# LAN_RJ45.net
KiCad netlist of a schematic drawn in Altium Designer
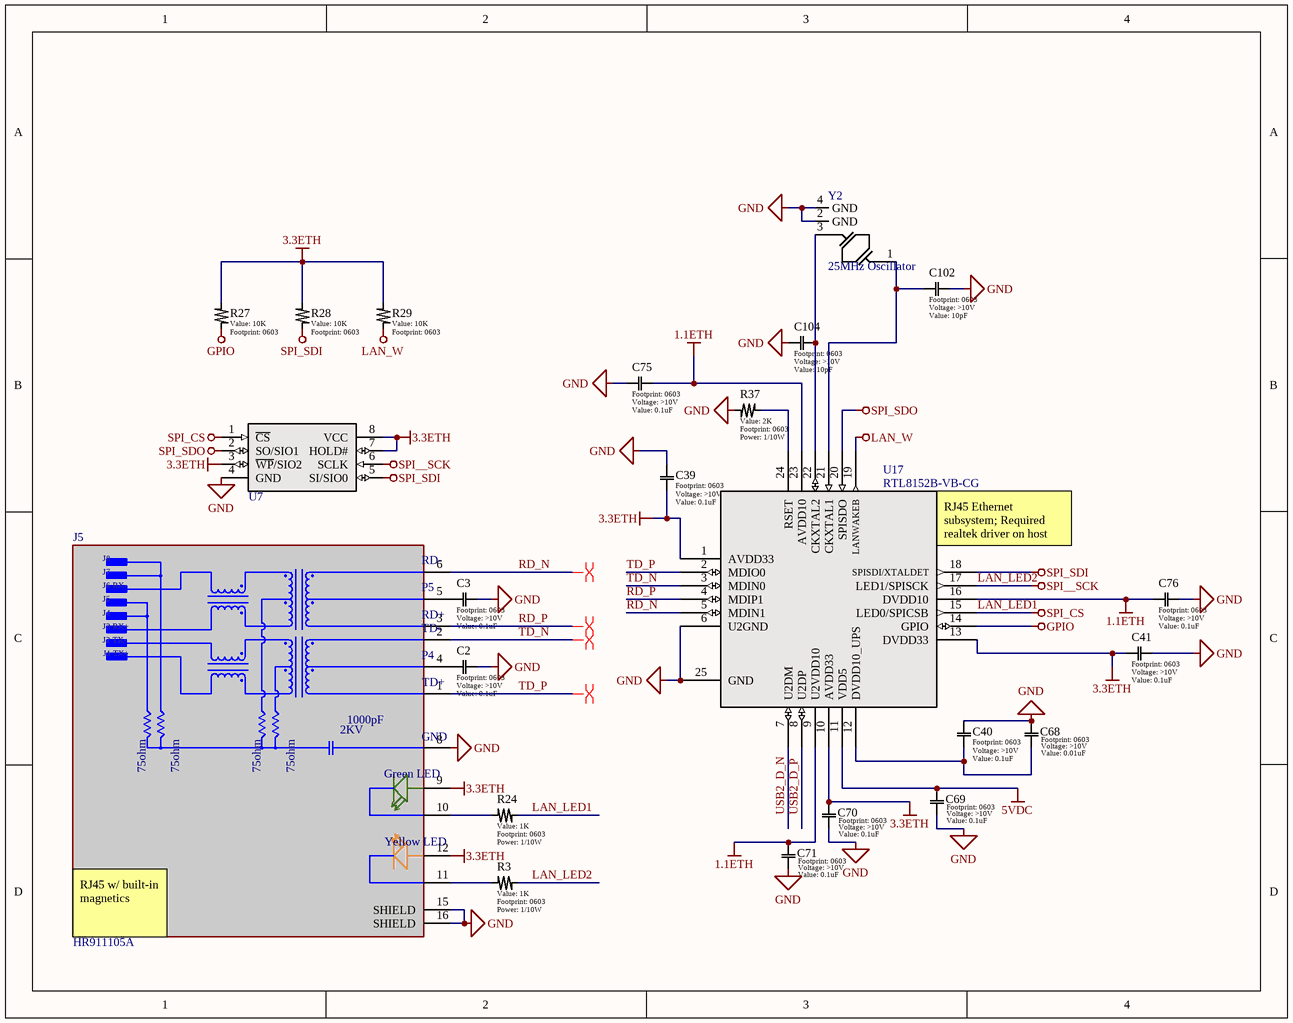
[diagram p0: LAN_RJ45.SchDoc]

(export (version "E")
  (design (tool "Eeschema 10.0.6"))
  (components
    (comp (ref "C2")
      (value "0.1uF")
      (footprint "0603")
      (fields
        (field (name "VOLTAGE") ">10V")
        (field (name "TOLERANCE") "10%")
        (field (name "Comment") "Generic Capacitor")
      )
      (libsource (lib "Capacitors") (part "Generic Capacitor"))
    )
    (comp (ref "C3")
      (value "0.1uF")
      (footprint "0603")
      (fields
        (field (name "VOLTAGE") ">10V")
        (field (name "TOLERANCE") "10%")
        (field (name "Comment") "Generic Capacitor")
      )
      (libsource (lib "Capacitors") (part "Generic Capacitor"))
    )
    (comp (ref "C39")
      (value "0.1uF")
      (footprint "0603")
      (fields
        (field (name "VOLTAGE") ">10V")
        (field (name "TOLERANCE") "10%")
        (field (name "Comment") "Generic Capacitor")
      )
      (libsource (lib "Capacitors") (part "Generic Capacitor"))
    )
    (comp (ref "C40")
      (value "0.1uF")
      (footprint "0603")
      (fields
        (field (name "VOLTAGE") ">10V")
        (field (name "TOLERANCE") "10%")
        (field (name "Comment") "Generic Capacitor")
      )
      (libsource (lib "Capacitors") (part "Generic Capacitor"))
    )
    (comp (ref "C41")
      (value "0.1uF")
      (footprint "0603")
      (fields
        (field (name "VOLTAGE") ">10V")
        (field (name "TOLERANCE") "10%")
        (field (name "Comment") "Generic Capacitor")
      )
      (libsource (lib "Capacitors") (part "Generic Capacitor"))
    )
    (comp (ref "C68")
      (value "0.01uF")
      (footprint "0603")
      (fields
        (field (name "VOLTAGE") ">10V")
        (field (name "TOLERANCE") "10%")
        (field (name "Comment") "Generic Capacitor")
      )
      (libsource (lib "Capacitors") (part "Generic Capacitor"))
    )
    (comp (ref "C69")
      (value "0.1uF")
      (footprint "0603")
      (fields
        (field (name "VOLTAGE") ">10V")
        (field (name "TOLERANCE") "10%")
        (field (name "Comment") "Generic Capacitor")
      )
      (libsource (lib "Capacitors") (part "Generic Capacitor"))
    )
    (comp (ref "C70")
      (value "0.1uF")
      (footprint "0603")
      (fields
        (field (name "VOLTAGE") ">10V")
        (field (name "TOLERANCE") "10%")
        (field (name "Comment") "Generic Capacitor")
      )
      (libsource (lib "Capacitors") (part "Generic Capacitor"))
    )
    (comp (ref "C71")
      (value "0.1uF")
      (footprint "0603")
      (fields
        (field (name "VOLTAGE") ">10V")
        (field (name "TOLERANCE") "10%")
        (field (name "Comment") "Generic Capacitor")
      )
      (libsource (lib "Capacitors") (part "Generic Capacitor"))
    )
    (comp (ref "C75")
      (value "0.1uF")
      (footprint "0603")
      (fields
        (field (name "VOLTAGE") ">10V")
        (field (name "TOLERANCE") "10%")
        (field (name "Comment") "Generic Capacitor")
      )
      (libsource (lib "Capacitors") (part "Generic Capacitor"))
    )
    (comp (ref "C76")
      (value "0.1uF")
      (footprint "0603")
      (fields
        (field (name "VOLTAGE") ">10V")
        (field (name "TOLERANCE") "10%")
        (field (name "Comment") "Generic Capacitor")
      )
      (libsource (lib "Capacitors") (part "Generic Capacitor"))
    )
    (comp (ref "C102")
      (value "10pF")
      (footprint "0603")
      (fields
        (field (name "VOLTAGE") ">10V")
        (field (name "TOLERANCE") "10%")
        (field (name "Comment") "Generic Capacitor")
      )
      (libsource (lib "Capacitors") (part "Generic Capacitor"))
    )
    (comp (ref "C104")
      (value "10pF")
      (footprint "0603")
      (fields
        (field (name "VOLTAGE") ">10V")
        (field (name "TOLERANCE") "10%")
        (field (name "Comment") "Generic Capacitor")
      )
      (libsource (lib "Capacitors") (part "Generic Capacitor"))
    )
    (comp (ref "J5")
      (value "HR911105A")
      (footprint "HR911105A")
      (description "RJ45 Receptacle 1 WithLED Plugin Ethernet")
      (libsource (lib "Connectors") (part "HR911105A"))
    )
    (comp (ref "R3")
      (value "1K")
      (footprint "0603")
      (fields
        (field (name "TOLERANCE") "1%")
        (field (name "POWER") "1/10W")
        (field (name "Comment") "Generic Resistor")
      )
      (libsource (lib "Resistors") (part "Generic Resistor"))
    )
    (comp (ref "R24")
      (value "1K")
      (footprint "0603")
      (fields
        (field (name "TOLERANCE") "1%")
        (field (name "POWER") "1/10W")
        (field (name "Comment") "Generic Resistor")
      )
      (libsource (lib "Resistors") (part "Generic Resistor"))
    )
    (comp (ref "R27")
      (value "10K")
      (footprint "0603")
      (fields
        (field (name "TOLERANCE") "1%")
        (field (name "POWER") "1/10W")
        (field (name "Comment") "Generic Resistor")
      )
      (libsource (lib "Resistors") (part "Generic Resistor"))
    )
    (comp (ref "R28")
      (value "10K")
      (footprint "0603")
      (fields
        (field (name "TOLERANCE") "1%")
        (field (name "POWER") "1/10W")
        (field (name "Comment") "Generic Resistor")
      )
      (libsource (lib "Resistors") (part "Generic Resistor"))
    )
    (comp (ref "R29")
      (value "10K")
      (footprint "0603")
      (fields
        (field (name "TOLERANCE") "1%")
        (field (name "POWER") "1/10W")
        (field (name "Comment") "Generic Resistor")
      )
      (libsource (lib "Resistors") (part "Generic Resistor"))
    )
    (comp (ref "R37")
      (value "2K")
      (footprint "0603")
      (fields
        (field (name "TOLERANCE") "1%")
        (field (name "POWER") "1/10W")
        (field (name "Comment") "Generic Resistor")
      )
      (libsource (lib "Resistors") (part "Generic Resistor"))
    )
    (comp (ref "U7")
      (value "FlashMem")
      (footprint "8-SOIC (0.209\", 5.30mm WIDTH)")
      (description "16Mbit SPI SOIC-8-208mil NOR FLASH")
      (libsource (lib "Misc ICs") (part "MX25L1606EM2I-12G"))
    )
    (comp (ref "U17")
      (value "RTL8152B-VB-CG")
      (footprint "RTL8152B-VB-CG")
      (libsource (lib "Misc ICs") (part "RTL8152B-VB-CG"))
    )
    (comp (ref "Y2")
      (value "25MHz Oscillator")
      (footprint "ABM8G-25.000MHZ-B4Y-T")
      (description "25 MHz ±30ppm Crystal 10pF 60 Ohms 4-SMD, No Lead\r\nSMD3225-4P")
      (fields
        (field (name "MANUFACTURER") "Abracon")
        (field (name "MANUFACTURER PART NUMBER") "ABM8G-25.000MHZ-B4Y-T")
      )
      (libsource (lib "Misc ICs") (part "ABM8G-25.000MHZ-B4Y-T"))
    )
  )
  (nets
    (net (code "1") (name "/RD_N") (class "Default")
      (node (ref "J5") (pin "6") (pinfunction "RD-_6") (pintype "passive"))
      (node (ref "U17") (pin "5") (pinfunction "MDIN1_5") (pintype "bidirectional"))
    )
    (net (code "2") (name "/RD_P") (class "Default")
      (node (ref "J5") (pin "3") (pinfunction "RD+_3") (pintype "passive"))
      (node (ref "U17") (pin "4") (pinfunction "MDIP1_4") (pintype "bidirectional"))
    )
    (net (code "3") (name "/TD_N") (class "Default")
      (node (ref "J5") (pin "2") (pinfunction "TD-_2") (pintype "passive"))
      (node (ref "U17") (pin "3") (pinfunction "MDIN0_3") (pintype "bidirectional"))
    )
    (net (code "4") (name "/TD_P") (class "Default")
      (node (ref "J5") (pin "1") (pinfunction "TD+_1") (pintype "passive"))
      (node (ref "U17") (pin "2") (pinfunction "MDIO0_2") (pintype "bidirectional"))
    )
    (net (code "5") (name "/USB2_D_N") (class "Default")
      (node (ref "U17") (pin "7") (pinfunction "U2DM_7") (pintype "bidirectional"))
    )
    (net (code "6") (name "/USB2_D_P") (class "Default")
      (node (ref "U17") (pin "8") (pinfunction "U2DP_8") (pintype "bidirectional"))
    )
    (net (code "7") (name "1.1ETH") (class "Default")
      (node (ref "C71") (pin "1") (pinfunction "1_1") (pintype "passive"))
      (node (ref "C75") (pin "1") (pinfunction "1_1") (pintype "passive"))
      (node (ref "C76") (pin "2") (pinfunction "2_2") (pintype "passive"))
      (node (ref "U17") (pin "16") (pinfunction "DVDD10_16") (pintype "power_in"))
      (node (ref "U17") (pin "23") (pinfunction "AVDD10_23") (pintype "power_in"))
      (node (ref "U17") (pin "9") (pinfunction "U2VDD10_9") (pintype "power_in"))
    )
    (net (code "8") (name "3.3ETH") (class "Default")
      (node (ref "C39") (pin "1") (pinfunction "1_1") (pintype "passive"))
      (node (ref "C41") (pin "2") (pinfunction "2_2") (pintype "passive"))
      (node (ref "C70") (pin "1") (pinfunction "1_1") (pintype "passive"))
      (node (ref "J5") (pin "12") (pinfunction "YA_12") (pintype "passive"))
      (node (ref "J5") (pin "9") (pinfunction "GA_9") (pintype "passive"))
      (node (ref "R27") (pin "1") (pinfunction "1_1") (pintype "passive"))
      (node (ref "R28") (pin "1") (pinfunction "1_1") (pintype "passive"))
      (node (ref "R29") (pin "1") (pinfunction "1_1") (pintype "passive"))
      (node (ref "U17") (pin "1") (pinfunction "AVDD33_1") (pintype "power_in"))
      (node (ref "U17") (pin "10") (pinfunction "AVDD33_10") (pintype "power_in"))
      (node (ref "U17") (pin "13") (pinfunction "DVDD33_13") (pintype "power_in"))
      (node (ref "U7") (pin "3") (pinfunction "~{WP}/SIO2_3") (pintype "bidirectional"))
      (node (ref "U7") (pin "7") (pinfunction "HOLD#_7") (pintype "bidirectional"))
      (node (ref "U7") (pin "8") (pinfunction "VCC_8") (pintype "power_in"))
    )
    (net (code "9") (name "5VDC") (class "Default")
      (node (ref "C69") (pin "1") (pinfunction "1_1") (pintype "passive"))
      (node (ref "U17") (pin "11") (pinfunction "VDD5_11") (pintype "power_in"))
    )
    (net (code "10") (name "GND") (class "Default")
      (node (ref "C102") (pin "1") (pinfunction "1_1") (pintype "passive"))
      (node (ref "C104") (pin "2") (pinfunction "2_2") (pintype "passive"))
      (node (ref "C2") (pin "1") (pinfunction "1_1") (pintype "passive"))
      (node (ref "C3") (pin "1") (pinfunction "1_1") (pintype "passive"))
      (node (ref "C39") (pin "2") (pinfunction "2_2") (pintype "passive"))
      (node (ref "C40") (pin "1") (pinfunction "1_1") (pintype "passive"))
      (node (ref "C41") (pin "1") (pinfunction "1_1") (pintype "passive"))
      (node (ref "C68") (pin "1") (pinfunction "1_1") (pintype "passive"))
      (node (ref "C69") (pin "2") (pinfunction "2_2") (pintype "passive"))
      (node (ref "C70") (pin "2") (pinfunction "2_2") (pintype "passive"))
      (node (ref "C71") (pin "2") (pinfunction "2_2") (pintype "passive"))
      (node (ref "C75") (pin "2") (pinfunction "2_2") (pintype "passive"))
      (node (ref "C76") (pin "1") (pinfunction "1_1") (pintype "passive"))
      (node (ref "J5") (pin "15") (pinfunction "SHIELD_15") (pintype "passive"))
      (node (ref "J5") (pin "16") (pinfunction "SHIELD_16") (pintype "passive"))
      (node (ref "J5") (pin "8") (pinfunction "GND_8") (pintype "power_in"))
      (node (ref "R37") (pin "1") (pinfunction "1_1") (pintype "passive"))
      (node (ref "U17") (pin "25") (pinfunction "GND_25") (pintype "passive"))
      (node (ref "U17") (pin "6") (pinfunction "U2GND_6") (pintype "passive"))
      (node (ref "U7") (pin "4") (pinfunction "GND_4") (pintype "power_in"))
      (node (ref "Y2") (pin "2") (pinfunction "GND_2") (pintype "passive"))
      (node (ref "Y2") (pin "4") (pinfunction "GND_4") (pintype "passive"))
    )
    (net (code "11") (name "GPIO") (class "Default")
      (node (ref "R27") (pin "2") (pinfunction "2_2") (pintype "passive"))
      (node (ref "U17") (pin "14") (pinfunction "GPIO_14") (pintype "bidirectional"))
    )
    (net (code "12") (name "LAN_W") (class "Default")
      (node (ref "R29") (pin "2") (pinfunction "2_2") (pintype "passive"))
      (node (ref "U17") (pin "19") (pinfunction "LANWAKEB_19") (pintype "output"))
    )
    (net (code "13") (name "Net-(J5-GC)") (class "Default")
      (node (ref "J5") (pin "10") (pinfunction "GC_10") (pintype "passive"))
      (node (ref "R24") (pin "1") (pinfunction "1_1") (pintype "passive"))
    )
    (net (code "14") (name "Net-(J5-P4)") (class "Default")
      (node (ref "C2") (pin "2") (pinfunction "2_2") (pintype "passive"))
      (node (ref "J5") (pin "4") (pinfunction "P4_4") (pintype "passive"))
    )
    (net (code "15") (name "Net-(J5-P5)") (class "Default")
      (node (ref "C3") (pin "2") (pinfunction "2_2") (pintype "passive"))
      (node (ref "J5") (pin "5") (pinfunction "P5_5") (pintype "passive"))
    )
    (net (code "16") (name "Net-(J5-YC)") (class "Default")
      (node (ref "J5") (pin "11") (pinfunction "YC_11") (pintype "passive"))
      (node (ref "R3") (pin "1") (pinfunction "1_1") (pintype "passive"))
    )
    (net (code "17") (name "Net-(U17-CKXTAL1)") (class "Default")
      (node (ref "C102") (pin "2") (pinfunction "2_2") (pintype "passive"))
      (node (ref "U17") (pin "21") (pinfunction "CKXTAL1_21") (pintype "input"))
      (node (ref "Y2") (pin "1") (pinfunction "1_1") (pintype "passive"))
    )
    (net (code "18") (name "Net-(U17-CKXTAL2)") (class "Default")
      (node (ref "C104") (pin "1") (pinfunction "1_1") (pintype "passive"))
      (node (ref "U17") (pin "22") (pinfunction "CKXTAL2_22") (pintype "bidirectional"))
      (node (ref "Y2") (pin "3") (pinfunction "3_3") (pintype "passive"))
    )
    (net (code "19") (name "Net-(U17-DVDD10_UPS)") (class "Default")
      (node (ref "C40") (pin "2") (pinfunction "2_2") (pintype "passive"))
      (node (ref "C68") (pin "2") (pinfunction "2_2") (pintype "passive"))
      (node (ref "U17") (pin "12") (pinfunction "DVDD10_UPS_12") (pintype "power_in"))
    )
    (net (code "20") (name "Net-(U17-RSET)") (class "Default")
      (node (ref "R37") (pin "2") (pinfunction "2_2") (pintype "passive"))
      (node (ref "U17") (pin "24") (pinfunction "RSET_24") (pintype "power_in"))
    )
    (net (code "21") (name "SPI_CS") (class "Default")
      (node (ref "R24") (pin "2") (pinfunction "2_2") (pintype "passive"))
      (node (ref "U17") (pin "15") (pinfunction "LED0/SPICSB_15") (pintype "output"))
      (node (ref "U7") (pin "1") (pinfunction "~{CS}_1") (pintype "input"))
    )
    (net (code "22") (name "SPI_SDI") (class "Default")
      (node (ref "R28") (pin "2") (pinfunction "2_2") (pintype "passive"))
      (node (ref "U17") (pin "18") (pinfunction "SPISDI/XTALDET_18") (pintype "output"))
      (node (ref "U7") (pin "5") (pinfunction "SI/SIO0_5") (pintype "bidirectional"))
    )
    (net (code "23") (name "SPI_SDO") (class "Default")
      (node (ref "U17") (pin "20") (pinfunction "SPISDO_20") (pintype "input"))
      (node (ref "U7") (pin "2") (pinfunction "SO/SIO1_2") (pintype "bidirectional"))
    )
    (net (code "24") (name "SPI__SCK") (class "Default")
      (node (ref "R3") (pin "2") (pinfunction "2_2") (pintype "passive"))
      (node (ref "U17") (pin "17") (pinfunction "LED1/SPISCK_17") (pintype "output"))
      (node (ref "U7") (pin "6") (pinfunction "SCLK_6") (pintype "input"))
    )
  )
)
